# CAN.net
KiCad netlist of a schematic drawn in Altium Designer
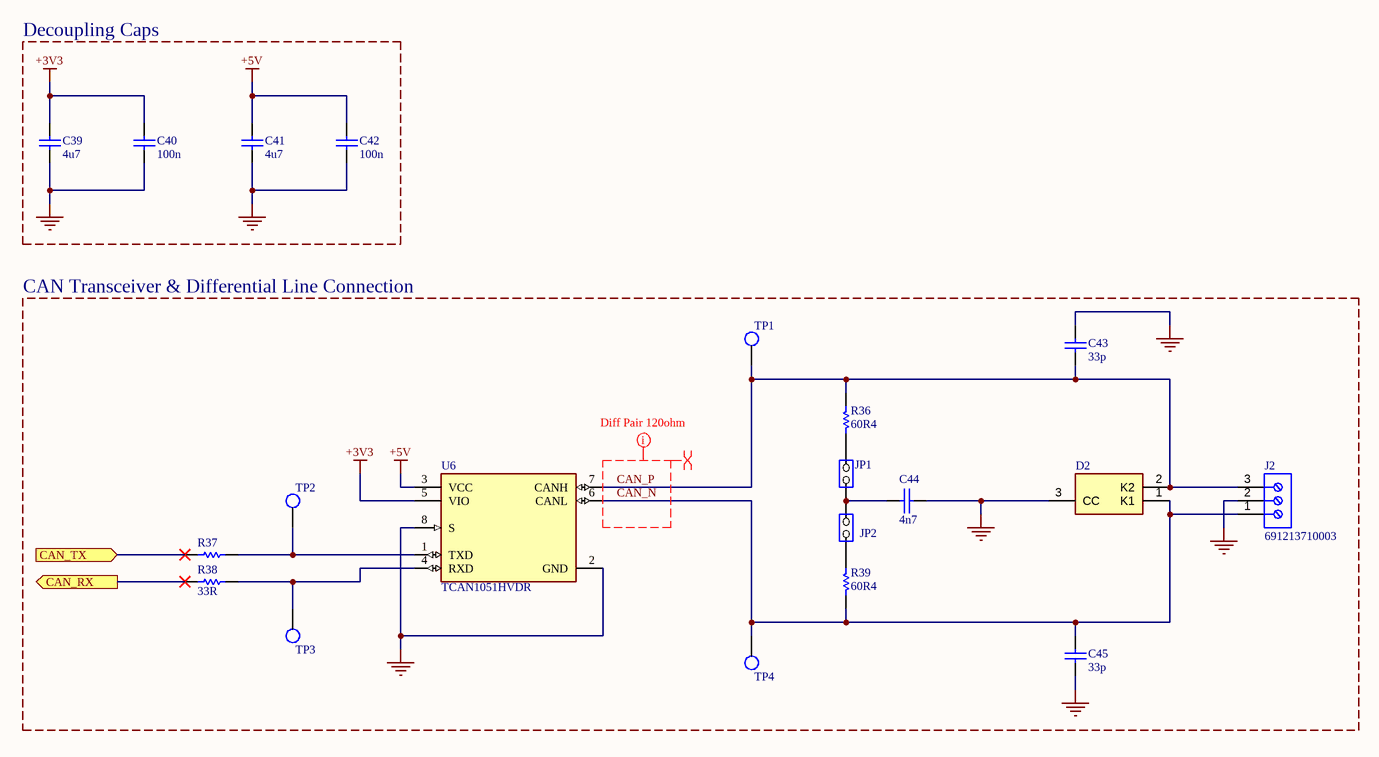
[diagram p0: CAN.SchDoc]

(export (version "E")
  (design (tool "Eeschema 10.0.6"))
  (components
    (comp (ref "C39")
      (value "4u7")
      (footprint "0603C")
      (description "Capacitor")
      (fields (field (name "TOLERANCE") "10%"))
      (libsource (lib "MB963_1") (part "CAP SMD 0603  X5R 1µF 25V 10%"))
    )
    (comp (ref "C40")
      (value "100n")
      (footprint "0603C")
      (description "Capacitor")
      (fields (field (name "PUBLISHER") "Altium Limited"))
      (libsource (lib "Miscellaneous Devices") (part "Cap"))
    )
    (comp (ref "C41")
      (value "4u7")
      (footprint "0603C")
      (description "Capacitor")
      (fields (field (name "TOLERANCE") "10%"))
      (libsource (lib "MB963_1") (part "CAP SMD 0603  X5R 1µF 25V 10%"))
    )
    (comp (ref "C42")
      (value "100n")
      (footprint "0603C")
      (description "Capacitor")
      (fields (field (name "PUBLISHER") "Altium Limited"))
      (libsource (lib "Miscellaneous Devices") (part "Cap"))
    )
    (comp (ref "C43")
      (value "33p")
      (footprint "0603C")
      (description "Capacitor")
      (fields (field (name "PUBLISHER") "Altium Limited"))
      (libsource (lib "Miscellaneous Devices") (part "Cap"))
    )
    (comp (ref "C44")
      (value "4n7")
      (footprint "0603C")
      (description "Capacitor")
      (libsource (lib "*") (part "CAP"))
    )
    (comp (ref "C45")
      (value "33p")
      (footprint "0603C")
      (description "Capacitor")
      (fields (field (name "PUBLISHER") "Altium Limited"))
      (libsource (lib "Miscellaneous Devices") (part "Cap"))
    )
    (comp (ref "D2")
      (value "PESD2CANFD24LT-QR")
      (footprint "SOT95P230X110-3N")
      (description "vp_PESD2CANFD24LT-Q - ESD protection for In-vehicle networks@en-us")
      (fields (field (name "MOUSER PART NUMBER") "771-PESD2CANFD24LTQR"))
      (libsource (lib "PESD2CANFD24LT-QR") (part "PESD2CANFD24LT-QR"))
    )
    (comp (ref "J2")
      (value "691213710003")
      (footprint "691213710003")
      (description "213 Series 5MM Pitch Straight, Pcb Terminal Block, Through Hole, 3 Way")
      (fields (field (name "VOLTAGE") "300V"))
      (libsource (lib "Altium Content Vault") (part "TBL - 1R - 03P - Screw"))
    )
    (comp (ref "JP1") (value "~") (footprint "HDR_1x2_2R54_V_M_S") (libsource (lib "MB1137") (part "JP2")))
    (comp (ref "JP2") (value "~") (footprint "HDR_1x2_2R54_V_M_S") (libsource (lib "MB1137") (part "JP2")))
    (comp (ref "R36")
      (value "60R4")
      (footprint "0603R")
      (description "Resistor")
      (fields (field (name "PUBLISHER") "Altium Limited"))
      (libsource (lib "Miscellaneous Devices") (part "res1"))
    )
    (comp (ref "R37")
      (value "33R")
      (footprint "0603R")
      (description "Resistor")
      (fields (field (name "TOLERANCE") "1%") (field (name "PUBLISHER") "Altium Limited"))
      (libsource (lib "Miscellaneous Devices") (part "res1"))
    )
    (comp (ref "R38")
      (value "33R")
      (footprint "0603R")
      (description "Resistor")
      (fields (field (name "TOLERANCE") "1%") (field (name "PUBLISHER") "Altium Limited"))
      (libsource (lib "Miscellaneous Devices") (part "res1"))
    )
    (comp (ref "R39")
      (value "60R4")
      (footprint "0603R")
      (description "Resistor")
      (fields (field (name "PUBLISHER") "Altium Limited"))
      (libsource (lib "Miscellaneous Devices") (part "res1"))
    )
    (comp (ref "TP1")
      (value "Test Point")
      (footprint "TP_SMD_0.8")
      (libsource (lib "FinalProject") (part "Test_Point"))
    )
    (comp (ref "TP2")
      (value "Test Point")
      (footprint "TP_SMD_0.8")
      (libsource (lib "FinalProject") (part "Test_Point"))
    )
    (comp (ref "TP3")
      (value "Test Point")
      (footprint "TP_SMD_0.8")
      (libsource (lib "FinalProject") (part "Test_Point"))
    )
    (comp (ref "TP4")
      (value "Test Point")
      (footprint "TP_SMD_0.8")
      (libsource (lib "FinalProject") (part "Test_Point"))
    )
    (comp (ref "U6")
      (value "TCAN1051HVDR")
      (footprint "FP-D0008B-IPC_B")
      (description "IC TRANSCEIVER HALF 1/1 8SOIC")
      (libsource (lib "Altium Content Vault") (part "2f30dca45018ede40f5142a305e9498"))
    )
  )
  (nets
    (net (code "1") (name "+3V3") (class "Default")
      (node (ref "C39") (pin "1") (pinfunction "1_1") (pintype "passive"))
      (node (ref "C40") (pin "1") (pinfunction "1_1") (pintype "passive"))
      (node (ref "U6") (pin "5") (pinfunction "VIO_5") (pintype "power_in"))
    )
    (net (code "2") (name "+5V") (class "Default")
      (node (ref "C41") (pin "1") (pinfunction "1_1") (pintype "passive"))
      (node (ref "C42") (pin "1") (pinfunction "1_1") (pintype "passive"))
      (node (ref "U6") (pin "3") (pinfunction "VCC_3") (pintype "power_in"))
    )
    (net (code "3") (name "/CAN_N") (class "Default")
      (node (ref "C45") (pin "2") (pinfunction "2_2") (pintype "passive"))
      (node (ref "D2") (pin "1") (pinfunction "K1_1") (pintype "passive"))
      (node (ref "J2") (pin "1") (pinfunction "1_1") (pintype "passive"))
      (node (ref "R39") (pin "1") (pinfunction "1_1") (pintype "passive"))
      (node (ref "TP4") (pin "1") (pintype "passive"))
      (node (ref "U6") (pin "6") (pinfunction "CANL_6") (pintype "bidirectional"))
    )
    (net (code "4") (name "/CAN_P") (class "Default")
      (node (ref "C43") (pin "1") (pinfunction "1_1") (pintype "passive"))
      (node (ref "D2") (pin "2") (pinfunction "K2_2") (pintype "passive"))
      (node (ref "J2") (pin "3") (pinfunction "3_3") (pintype "passive"))
      (node (ref "R36") (pin "2") (pinfunction "2_2") (pintype "passive"))
      (node (ref "TP1") (pin "1") (pintype "passive"))
      (node (ref "U6") (pin "7") (pinfunction "CANH_7") (pintype "bidirectional"))
    )
    (net (code "5") (name "/CAN_RX") (class "Default")
      (node (ref "R38") (pin "1") (pinfunction "1_1") (pintype "passive+no_connect"))
    )
    (net (code "6") (name "/CAN_TX") (class "Default")
      (node (ref "R37") (pin "1") (pinfunction "1_1") (pintype "passive+no_connect"))
    )
    (net (code "7") (name "GND") (class "Default")
      (node (ref "C39") (pin "2") (pinfunction "2_2") (pintype "passive"))
      (node (ref "C40") (pin "2") (pinfunction "2_2") (pintype "passive"))
      (node (ref "C41") (pin "2") (pinfunction "2_2") (pintype "passive"))
      (node (ref "C42") (pin "2") (pinfunction "2_2") (pintype "passive"))
      (node (ref "C43") (pin "2") (pinfunction "2_2") (pintype "passive"))
      (node (ref "C44") (pin "2") (pinfunction "2_2") (pintype "passive"))
      (node (ref "C45") (pin "1") (pinfunction "1_1") (pintype "passive"))
      (node (ref "D2") (pin "3") (pinfunction "CC_3") (pintype "passive"))
      (node (ref "J2") (pin "2") (pinfunction "2_2") (pintype "passive"))
      (node (ref "U6") (pin "2") (pinfunction "GND_2") (pintype "power_in"))
      (node (ref "U6") (pin "8") (pinfunction "S_8") (pintype "input"))
    )
    (net (code "8") (name "Net-(JP1-COMMON)") (class "Default")
      (node (ref "C44") (pin "1") (pinfunction "1_1") (pintype "passive"))
      (node (ref "JP1") (pin "1") (pinfunction "COMMON_1") (pintype "passive"))
      (node (ref "JP2") (pin "2") (pinfunction "NO_2") (pintype "passive"))
    )
    (net (code "9") (name "Net-(JP1-NO)") (class "Default")
      (node (ref "JP1") (pin "2") (pinfunction "NO_2") (pintype "passive"))
      (node (ref "R36") (pin "1") (pinfunction "1_1") (pintype "passive"))
    )
    (net (code "10") (name "Net-(JP2-COMMON)") (class "Default")
      (node (ref "JP2") (pin "1") (pinfunction "COMMON_1") (pintype "passive"))
      (node (ref "R39") (pin "2") (pinfunction "2_2") (pintype "passive"))
    )
    (net (code "11") (name "Net-(U6-RXD)") (class "Default")
      (node (ref "R38") (pin "2") (pinfunction "2_2") (pintype "passive"))
      (node (ref "TP3") (pin "1") (pintype "passive"))
      (node (ref "U6") (pin "4") (pinfunction "RXD_4") (pintype "bidirectional"))
    )
    (net (code "12") (name "Net-(U6-TXD)") (class "Default")
      (node (ref "R37") (pin "2") (pinfunction "2_2") (pintype "passive"))
      (node (ref "TP2") (pin "1") (pintype "passive"))
      (node (ref "U6") (pin "1") (pinfunction "TXD_1") (pintype "bidirectional"))
    )
  )
)
